# as5040_encoder_1_0.net
KiCad netlist of a schematic drawn in EAGLE
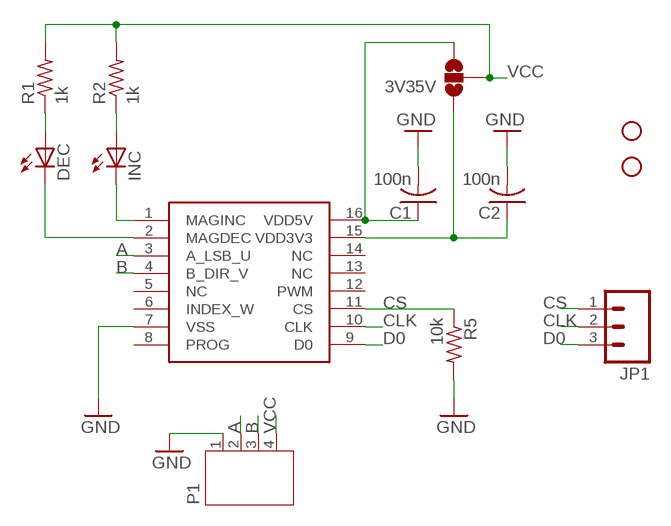
[diagram p0: schematic, sheet 1]

(export (version "E")
  (design (tool "Eeschema 10.0.6"))
  (components
    (comp (ref "3V35V")
      (value "SOLDERJUMPER_2WAYPASTE1&2&3")
      (footprint "eagle-import:SJ_3_PASTE1&2&3")
      (libsource (lib "eagle-import") (part "SOLDERJUMPER_2WAYPASTE1&2&3"))
    )
    (comp (ref "5040")
      (value "AS5040")
      (footprint "eagle-import:SSOP16")
      (libsource (lib "eagle-import") (part "AS5040"))
    )
    (comp (ref "C1")
      (value "100n")
      (footprint "eagle-import:C0603K")
      (libsource (lib "eagle-import") (part "C-USC0603K"))
    )
    (comp (ref "C2")
      (value "100n")
      (footprint "eagle-import:C0603K")
      (libsource (lib "eagle-import") (part "C-USC0603K"))
    )
    (comp (ref "DEC")
      (value "LEDCHIPLED_0603")
      (footprint "eagle-import:CHIPLED_0603")
      (libsource (lib "eagle-import") (part "LEDCHIPLED_0603"))
    )
    (comp (ref "INC")
      (value "LEDCHIPLED_0603")
      (footprint "eagle-import:CHIPLED_0603")
      (libsource (lib "eagle-import") (part "LEDCHIPLED_0603"))
    )
    (comp (ref "JP1")
      (value "M03PTH")
      (footprint "eagle-import:1X03")
      (libsource (lib "eagle-import") (part "M03PTH"))
    )
    (comp (ref "P1")
      (value "JST-PH4")
      (footprint "eagle-import:JST-PH4")
      (libsource (lib "eagle-import") (part "JST-PH4"))
    )
    (comp (ref "R1")
      (value "1k")
      (footprint "eagle-import:R0603")
      (libsource (lib "eagle-import") (part "R-US_R0603"))
    )
    (comp (ref "R2")
      (value "1k")
      (footprint "eagle-import:R0603")
      (libsource (lib "eagle-import") (part "R-US_R0603"))
    )
    (comp (ref "R5")
      (value "10k")
      (footprint "eagle-import:R0603")
      (libsource (lib "eagle-import") (part "R-US_R0603"))
    )
    (comp (ref "STANDOFF1")
      (value "STAND-OFF")
      (footprint "eagle-import:STAND-OFF")
      (libsource (lib "eagle-import") (part "STAND-OFF"))
    )
    (comp (ref "STANDOFF2")
      (value "STAND-OFF")
      (footprint "eagle-import:STAND-OFF")
      (libsource (lib "eagle-import") (part "STAND-OFF"))
    )
  )
  (nets
    (net (code "1") (name "/A") (class "Default")
      (node (ref "5040") (pin "3") (pinfunction "A_LSB_U_3") (pintype "bidirectional"))
      (node (ref "P1") (pin "2") (pinfunction "2_2") (pintype "passive"))
    )
    (net (code "2") (name "/B") (class "Default")
      (node (ref "5040") (pin "4") (pinfunction "B_DIR_V_4") (pintype "bidirectional"))
      (node (ref "P1") (pin "3") (pinfunction "3_3") (pintype "passive"))
    )
    (net (code "3") (name "/CLK") (class "Default")
      (node (ref "5040") (pin "10") (pinfunction "CLK_10") (pintype "bidirectional"))
      (node (ref "JP1") (pin "2") (pinfunction "2_2") (pintype "passive"))
    )
    (net (code "4") (name "/CS") (class "Default")
      (node (ref "5040") (pin "11") (pinfunction "CS_11") (pintype "bidirectional"))
      (node (ref "JP1") (pin "1") (pinfunction "1_1") (pintype "passive"))
      (node (ref "R5") (pin "1") (pinfunction "1_1") (pintype "passive"))
    )
    (net (code "5") (name "/D0") (class "Default")
      (node (ref "5040") (pin "9") (pinfunction "D0_9") (pintype "bidirectional"))
      (node (ref "JP1") (pin "3") (pinfunction "3_3") (pintype "passive"))
    )
    (net (code "6") (name "/VCC") (class "Default")
      (node (ref "3V35V") (pin "2") (pinfunction "2_2") (pintype "passive"))
      (node (ref "P1") (pin "4") (pinfunction "4_4") (pintype "passive"))
      (node (ref "R1") (pin "2") (pinfunction "2_2") (pintype "passive"))
      (node (ref "R2") (pin "2") (pinfunction "2_2") (pintype "passive"))
    )
    (net (code "7") (name "GND") (class "Default")
      (node (ref "5040") (pin "7") (pinfunction "VSS_7") (pintype "bidirectional"))
      (node (ref "C1") (pin "2") (pinfunction "2_2") (pintype "passive"))
      (node (ref "C2") (pin "2") (pinfunction "2_2") (pintype "passive"))
      (node (ref "P1") (pin "1") (pinfunction "1_1") (pintype "passive"))
      (node (ref "R5") (pin "2") (pinfunction "2_2") (pintype "passive"))
    )
    (net (code "8") (name "Net-(5040-MAGDEC)") (class "Default")
      (node (ref "5040") (pin "2") (pinfunction "MAGDEC_2") (pintype "bidirectional"))
      (node (ref "DEC") (pin "C") (pinfunction "C_C") (pintype "passive"))
    )
    (net (code "9") (name "Net-(5040-MAGINC)") (class "Default")
      (node (ref "5040") (pin "1") (pinfunction "MAGINC_1") (pintype "bidirectional"))
      (node (ref "INC") (pin "C") (pinfunction "C_C") (pintype "passive"))
    )
    (net (code "10") (name "Net-(5040-VDD3V3)") (class "Default")
      (node (ref "3V35V") (pin "1") (pinfunction "1_1") (pintype "passive"))
      (node (ref "5040") (pin "15") (pinfunction "VDD3V3_15") (pintype "bidirectional"))
      (node (ref "C2") (pin "1") (pinfunction "1_1") (pintype "passive"))
    )
    (net (code "11") (name "Net-(5040-VDD5V)") (class "Default")
      (node (ref "3V35V") (pin "3") (pinfunction "3_3") (pintype "passive"))
      (node (ref "5040") (pin "16") (pinfunction "VDD5V_16") (pintype "bidirectional"))
      (node (ref "C1") (pin "1") (pinfunction "1_1") (pintype "passive"))
    )
    (net (code "12") (name "Net-(DEC-PadA)") (class "Default")
      (node (ref "DEC") (pin "A") (pinfunction "A_A") (pintype "passive"))
      (node (ref "R1") (pin "1") (pinfunction "1_1") (pintype "passive"))
    )
    (net (code "13") (name "Net-(INC-PadA)") (class "Default")
      (node (ref "INC") (pin "A") (pinfunction "A_A") (pintype "passive"))
      (node (ref "R2") (pin "1") (pinfunction "1_1") (pintype "passive"))
    )
    (net (code "14") (name "unconnected-(5040-INDEX_W-Pad6)") (class "Default")
      (node (ref "5040") (pin "6") (pinfunction "INDEX_W_6") (pintype "bidirectional"))
    )
    (net (code "15") (name "unconnected-(5040-NC-Pad5)") (class "Default")
      (node (ref "5040") (pin "5") (pinfunction "NC_5") (pintype "bidirectional"))
    )
    (net (code "16") (name "unconnected-(5040-NC-Pad13)") (class "Default")
      (node (ref "5040") (pin "13") (pinfunction "NC_13") (pintype "bidirectional"))
    )
    (net (code "17") (name "unconnected-(5040-NC-Pad14)") (class "Default")
      (node (ref "5040") (pin "14") (pinfunction "NC_14") (pintype "bidirectional"))
    )
    (net (code "18") (name "unconnected-(5040-PROG-Pad8)") (class "Default")
      (node (ref "5040") (pin "8") (pinfunction "PROG_8") (pintype "bidirectional"))
    )
    (net (code "19") (name "unconnected-(5040-PWM-Pad12)") (class "Default")
      (node (ref "5040") (pin "12") (pinfunction "PWM_12") (pintype "bidirectional"))
    )
  )
)
